# eii-psu-thr-hole-psb-v1_1.net
KiCad netlist of a schematic drawn in EAGLE
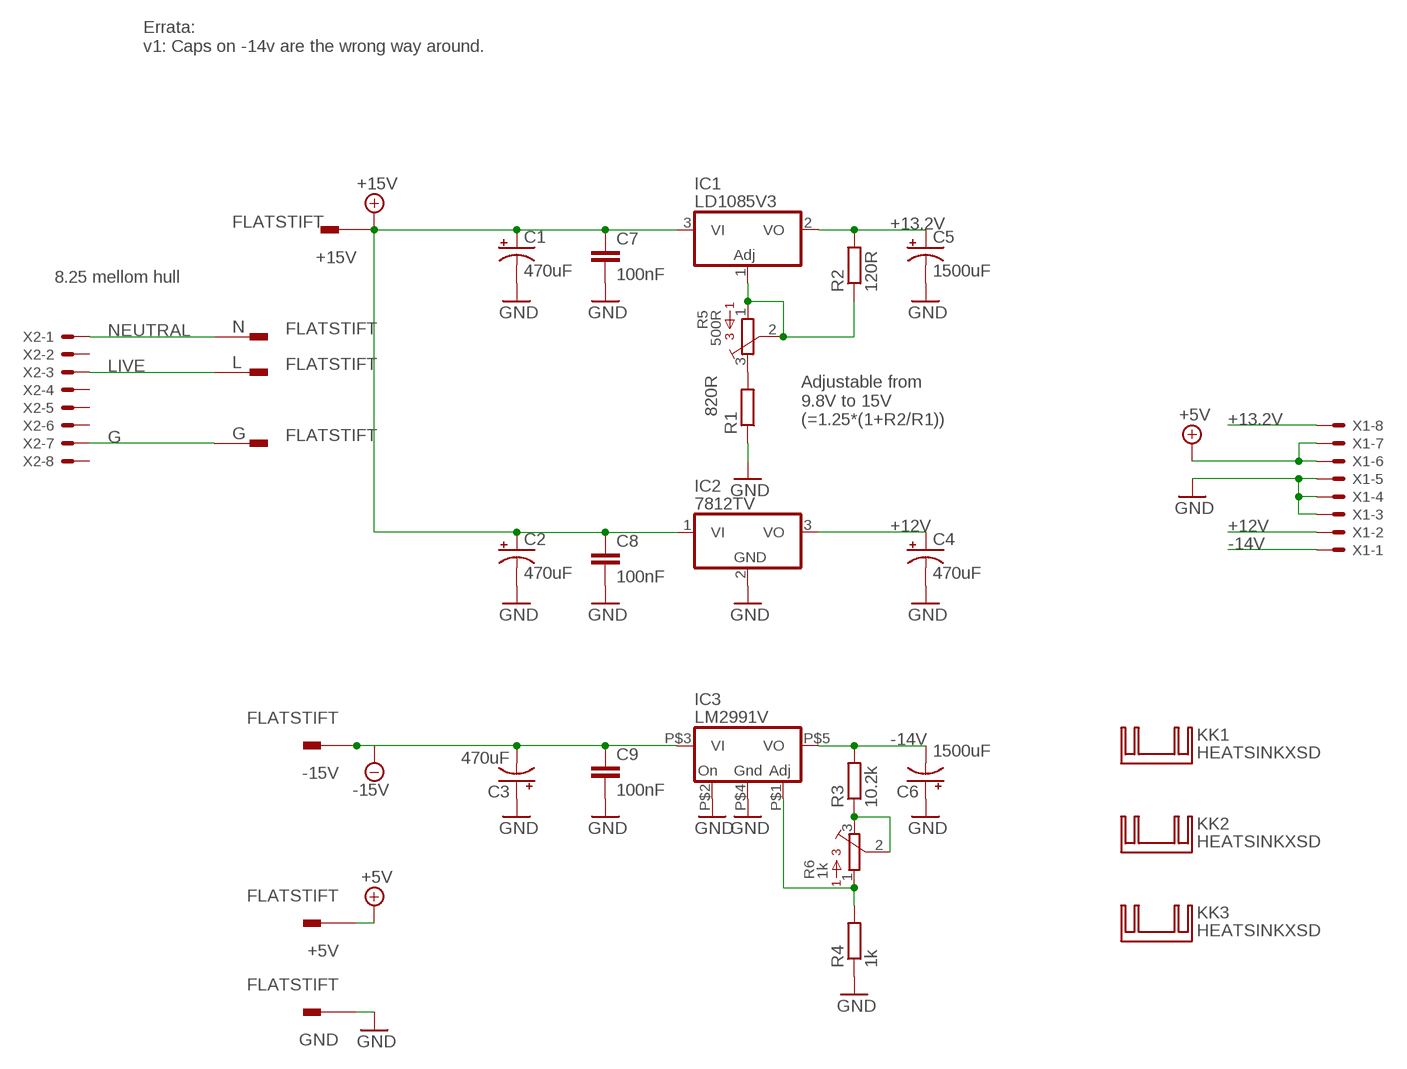
[diagram p0: schematic, sheet 1]

(export (version "E")
  (design (tool "Eeschema 10.0.6"))
  (components
    (comp (ref "+5V")
      (value "FLATSTIFT")
      (footprint "eagle-import:FLATSTIFT")
      (libsource (lib "eagle-import") (part "FLATSTIFT"))
    )
    (comp (ref "+15V")
      (value "FLATSTIFT")
      (footprint "eagle-import:FLATSTIFT")
      (libsource (lib "eagle-import") (part "FLATSTIFT"))
    )
    (comp (ref "-15V")
      (value "FLATSTIFT")
      (footprint "eagle-import:FLATSTIFT")
      (libsource (lib "eagle-import") (part "FLATSTIFT"))
    )
    (comp (ref "C1")
      (value "470uF")
      (footprint "eagle-import:E5-10,5")
      (libsource (lib "eagle-import") (part "CPOL-USE5-10.5"))
    )
    (comp (ref "C2")
      (value "470uF")
      (footprint "eagle-import:E5-10,5")
      (libsource (lib "eagle-import") (part "CPOL-USE5-10.5"))
    )
    (comp (ref "C3")
      (value "470uF")
      (footprint "eagle-import:E5-10,5")
      (libsource (lib "eagle-import") (part "CPOL-USE5-10.5"))
    )
    (comp (ref "C4")
      (value "470uF")
      (footprint "eagle-import:E5-10,5")
      (libsource (lib "eagle-import") (part "CPOL-USE5-10.5"))
    )
    (comp (ref "C5")
      (value "1500uF")
      (footprint "eagle-import:E5-13")
      (libsource (lib "eagle-import") (part "CPOL-USE5-13"))
    )
    (comp (ref "C6")
      (value "1500uF")
      (footprint "eagle-import:E5-13")
      (libsource (lib "eagle-import") (part "CPOL-USE5-13"))
    )
    (comp (ref "C7")
      (value "100nF")
      (footprint "eagle-import:C050-030X075")
      (libsource (lib "eagle-import") (part "C-EU050-030X075"))
    )
    (comp (ref "C8")
      (value "100nF")
      (footprint "eagle-import:C050-030X075")
      (libsource (lib "eagle-import") (part "C-EU050-030X075"))
    )
    (comp (ref "C9")
      (value "100nF")
      (footprint "eagle-import:C050-030X075")
      (libsource (lib "eagle-import") (part "C-EU050-030X075"))
    )
    (comp (ref "G")
      (value "FLATSTIFT")
      (footprint "eagle-import:FLATSTIFT")
      (libsource (lib "eagle-import") (part "FLATSTIFT"))
    )
    (comp (ref "GND")
      (value "FLATSTIFT")
      (footprint "eagle-import:FLATSTIFT")
      (libsource (lib "eagle-import") (part "FLATSTIFT"))
    )
    (comp (ref "IC1")
      (value "LD1085V3")
      (footprint "eagle-import:TO220V-J")
      (libsource (lib "eagle-import") (part "LD1085V3"))
    )
    (comp (ref "IC2")
      (value "7812TV")
      (footprint "eagle-import:TO220V")
      (libsource (lib "eagle-import") (part "78TV12"))
    )
    (comp (ref "IC3")
      (value "LM2991V")
      (footprint "eagle-import:TO220-5V-J")
      (libsource (lib "eagle-import") (part "LM2991V"))
    )
    (comp (ref "KK1")
      (value "HEATSINKXSD")
      (footprint "eagle-import:XSD1226-005")
      (libsource (lib "eagle-import") (part "HEATSINKXSD"))
    )
    (comp (ref "KK2")
      (value "HEATSINKXSD")
      (footprint "eagle-import:XSD1226-005")
      (libsource (lib "eagle-import") (part "HEATSINKXSD"))
    )
    (comp (ref "KK3")
      (value "HEATSINKXSD")
      (footprint "eagle-import:XSD1226-005")
      (libsource (lib "eagle-import") (part "HEATSINKXSD"))
    )
    (comp (ref "L")
      (value "FLATSTIFT")
      (footprint "eagle-import:FLATSTIFT")
      (libsource (lib "eagle-import") (part "FLATSTIFT"))
    )
    (comp (ref "N")
      (value "FLATSTIFT")
      (footprint "eagle-import:FLATSTIFT")
      (libsource (lib "eagle-import") (part "FLATSTIFT"))
    )
    (comp (ref "R1")
      (value "820R")
      (footprint "eagle-import:0207_7")
      (libsource (lib "eagle-import") (part "R-EU_0207/7"))
    )
    (comp (ref "R2")
      (value "120R")
      (footprint "eagle-import:0207_7")
      (libsource (lib "eagle-import") (part "R-EU_0207/7"))
    )
    (comp (ref "R3")
      (value "10.2k")
      (footprint "eagle-import:0207_7")
      (libsource (lib "eagle-import") (part "R-EU_0207/7"))
    )
    (comp (ref "R4")
      (value "1k")
      (footprint "eagle-import:0207_7")
      (libsource (lib "eagle-import") (part "R-EU_0207/7"))
    )
    (comp (ref "R5")
      (value "500R")
      (footprint "eagle-import:3362P")
      (libsource (lib "eagle-import") (part "3362P"))
    )
    (comp (ref "R6")
      (value "1k")
      (footprint "eagle-import:3362P")
      (libsource (lib "eagle-import") (part "3362P"))
    )
    (comp (ref "X1")
      (value "KK-156-8")
      (footprint "eagle-import:KK-156-8")
      (fields (field (name "MF") "MOLEX"))
      (libsource (lib "eagle-import") (part "KK-156-8"))
    )
    (comp (ref "X2")
      (value "KK-156-8")
      (footprint "eagle-import:KK-156-8")
      (fields (field (name "MF") "MOLEX"))
      (libsource (lib "eagle-import") (part "KK-156-8"))
    )
  )
  (nets
    (net (code "1") (name "+5V") (class "Default")
      (node (ref "+5V") (pin "F") (pinfunction "1_F") (pintype "passive"))
      (node (ref "+5V") (pin "F2") (pinfunction "1_F2") (pintype "passive"))
      (node (ref "X1") (pin "6") (pinfunction "S_6") (pintype "passive"))
      (node (ref "X1") (pin "7") (pinfunction "S_7") (pintype "passive"))
    )
    (net (code "2") (name "+15V") (class "Default")
      (node (ref "+15V") (pin "F") (pinfunction "1_F") (pintype "passive"))
      (node (ref "+15V") (pin "F2") (pinfunction "1_F2") (pintype "passive"))
      (node (ref "C1") (pin "+") (pinfunction "+_+") (pintype "passive"))
      (node (ref "C2") (pin "+") (pinfunction "+_+") (pintype "passive"))
      (node (ref "C7") (pin "1") (pinfunction "1_1") (pintype "passive"))
      (node (ref "C8") (pin "1") (pinfunction "1_1") (pintype "passive"))
      (node (ref "IC1") (pin "3") (pinfunction "VI_3") (pintype "input"))
      (node (ref "IC2") (pin "1") (pinfunction "VI_1") (pintype "input"))
    )
    (net (code "3") (name "-15V") (class "Default")
      (node (ref "-15V") (pin "F") (pinfunction "1_F") (pintype "passive"))
      (node (ref "-15V") (pin "F2") (pinfunction "1_F2") (pintype "passive"))
      (node (ref "C3") (pin "-") (pinfunction "-_-") (pintype "passive"))
      (node (ref "C9") (pin "1") (pinfunction "1_1") (pintype "passive"))
      (node (ref "IC3") (pin "P$3") (pinfunction "VI_P$3") (pintype "input"))
    )
    (net (code "4") (name "/+12V") (class "Default")
      (node (ref "C4") (pin "+") (pinfunction "+_+") (pintype "passive"))
      (node (ref "IC2") (pin "3") (pinfunction "VO_3") (pintype "passive"))
      (node (ref "X1") (pin "2") (pinfunction "S_2") (pintype "passive"))
    )
    (net (code "5") (name "/+13.2V") (class "Default")
      (node (ref "C5") (pin "+") (pinfunction "+_+") (pintype "passive"))
      (node (ref "IC1") (pin "2") (pinfunction "VO_2") (pintype "passive"))
      (node (ref "R2") (pin "2") (pinfunction "2_2") (pintype "passive"))
      (node (ref "X1") (pin "8") (pinfunction "S_8") (pintype "passive"))
    )
    (net (code "6") (name "/-14V") (class "Default")
      (node (ref "C6") (pin "-") (pinfunction "-_-") (pintype "passive"))
      (node (ref "IC3") (pin "P$5") (pinfunction "VO_P$5") (pintype "passive"))
      (node (ref "R3") (pin "2") (pinfunction "2_2") (pintype "passive"))
      (node (ref "X1") (pin "1") (pinfunction "S_1") (pintype "passive"))
    )
    (net (code "7") (name "/G") (class "Default")
      (node (ref "G") (pin "F") (pinfunction "1_F") (pintype "passive"))
      (node (ref "G") (pin "F2") (pinfunction "1_F2") (pintype "passive"))
      (node (ref "X2") (pin "7") (pinfunction "S_7") (pintype "passive"))
    )
    (net (code "8") (name "/LIVE") (class "Default")
      (node (ref "L") (pin "F") (pinfunction "1_F") (pintype "passive"))
      (node (ref "L") (pin "F2") (pinfunction "1_F2") (pintype "passive"))
      (node (ref "X2") (pin "3") (pinfunction "S_3") (pintype "passive"))
    )
    (net (code "9") (name "/NEUTRAL") (class "Default")
      (node (ref "N") (pin "F") (pinfunction "1_F") (pintype "passive"))
      (node (ref "N") (pin "F2") (pinfunction "1_F2") (pintype "passive"))
      (node (ref "X2") (pin "1") (pinfunction "S_1") (pintype "passive"))
    )
    (net (code "10") (name "GND") (class "Default")
      (node (ref "C1") (pin "-") (pinfunction "-_-") (pintype "passive"))
      (node (ref "C2") (pin "-") (pinfunction "-_-") (pintype "passive"))
      (node (ref "C3") (pin "+") (pinfunction "+_+") (pintype "passive"))
      (node (ref "C4") (pin "-") (pinfunction "-_-") (pintype "passive"))
      (node (ref "C5") (pin "-") (pinfunction "-_-") (pintype "passive"))
      (node (ref "C6") (pin "+") (pinfunction "+_+") (pintype "passive"))
      (node (ref "C7") (pin "2") (pinfunction "2_2") (pintype "passive"))
      (node (ref "C8") (pin "2") (pinfunction "2_2") (pintype "passive"))
      (node (ref "C9") (pin "2") (pinfunction "2_2") (pintype "passive"))
      (node (ref "GND") (pin "F") (pinfunction "1_F") (pintype "passive"))
      (node (ref "GND") (pin "F2") (pinfunction "1_F2") (pintype "passive"))
      (node (ref "IC2") (pin "2") (pinfunction "GND_2") (pintype "passive"))
      (node (ref "IC3") (pin "P$2") (pinfunction "ON_P$2") (pintype "passive"))
      (node (ref "IC3") (pin "P$4") (pinfunction "GND_P$4") (pintype "passive"))
      (node (ref "R1") (pin "1") (pinfunction "1_1") (pintype "passive"))
      (node (ref "R4") (pin "1") (pinfunction "1_1") (pintype "passive"))
      (node (ref "X1") (pin "3") (pinfunction "S_3") (pintype "passive"))
      (node (ref "X1") (pin "4") (pinfunction "S_4") (pintype "passive"))
      (node (ref "X1") (pin "5") (pinfunction "S_5") (pintype "passive"))
    )
    (net (code "11") (name "Net-(IC1-ADJ)") (class "Default")
      (node (ref "IC1") (pin "1") (pinfunction "ADJ_1") (pintype "passive"))
      (node (ref "R2") (pin "1") (pinfunction "1_1") (pintype "passive"))
      (node (ref "R5") (pin "1") (pinfunction "1_1") (pintype "passive"))
      (node (ref "R5") (pin "2") (pinfunction "2_2") (pintype "passive"))
    )
    (net (code "12") (name "Net-(IC3-ADJ)") (class "Default")
      (node (ref "IC3") (pin "P$1") (pinfunction "ADJ_P$1") (pintype "passive"))
      (node (ref "R4") (pin "2") (pinfunction "2_2") (pintype "passive"))
      (node (ref "R6") (pin "1") (pinfunction "1_1") (pintype "passive"))
    )
    (net (code "13") (name "Net-(R1-Pad2)") (class "Default")
      (node (ref "R1") (pin "2") (pinfunction "2_2") (pintype "passive"))
      (node (ref "R5") (pin "3") (pinfunction "3_3") (pintype "passive"))
    )
    (net (code "14") (name "Net-(R3-Pad1)") (class "Default")
      (node (ref "R3") (pin "1") (pinfunction "1_1") (pintype "passive"))
      (node (ref "R6") (pin "2") (pinfunction "2_2") (pintype "passive"))
      (node (ref "R6") (pin "3") (pinfunction "3_3") (pintype "passive"))
    )
    (net (code "15") (name "unconnected-(X2B-S-Pad2)") (class "Default")
      (node (ref "X2") (pin "2") (pinfunction "S_2") (pintype "passive"))
    )
    (net (code "16") (name "unconnected-(X2D-S-Pad4)") (class "Default")
      (node (ref "X2") (pin "4") (pinfunction "S_4") (pintype "passive"))
    )
    (net (code "17") (name "unconnected-(X2E-S-Pad5)") (class "Default")
      (node (ref "X2") (pin "5") (pinfunction "S_5") (pintype "passive"))
    )
    (net (code "18") (name "unconnected-(X2F-S-Pad6)") (class "Default")
      (node (ref "X2") (pin "6") (pinfunction "S_6") (pintype "passive"))
    )
    (net (code "19") (name "unconnected-(X2H-S-Pad8)") (class "Default")
      (node (ref "X2") (pin "8") (pinfunction "S_8") (pintype "passive"))
    )
  )
)
